# 1-Schematic_GPIO_WAVER.net
KiCad netlist of a schematic drawn in EasyEDA
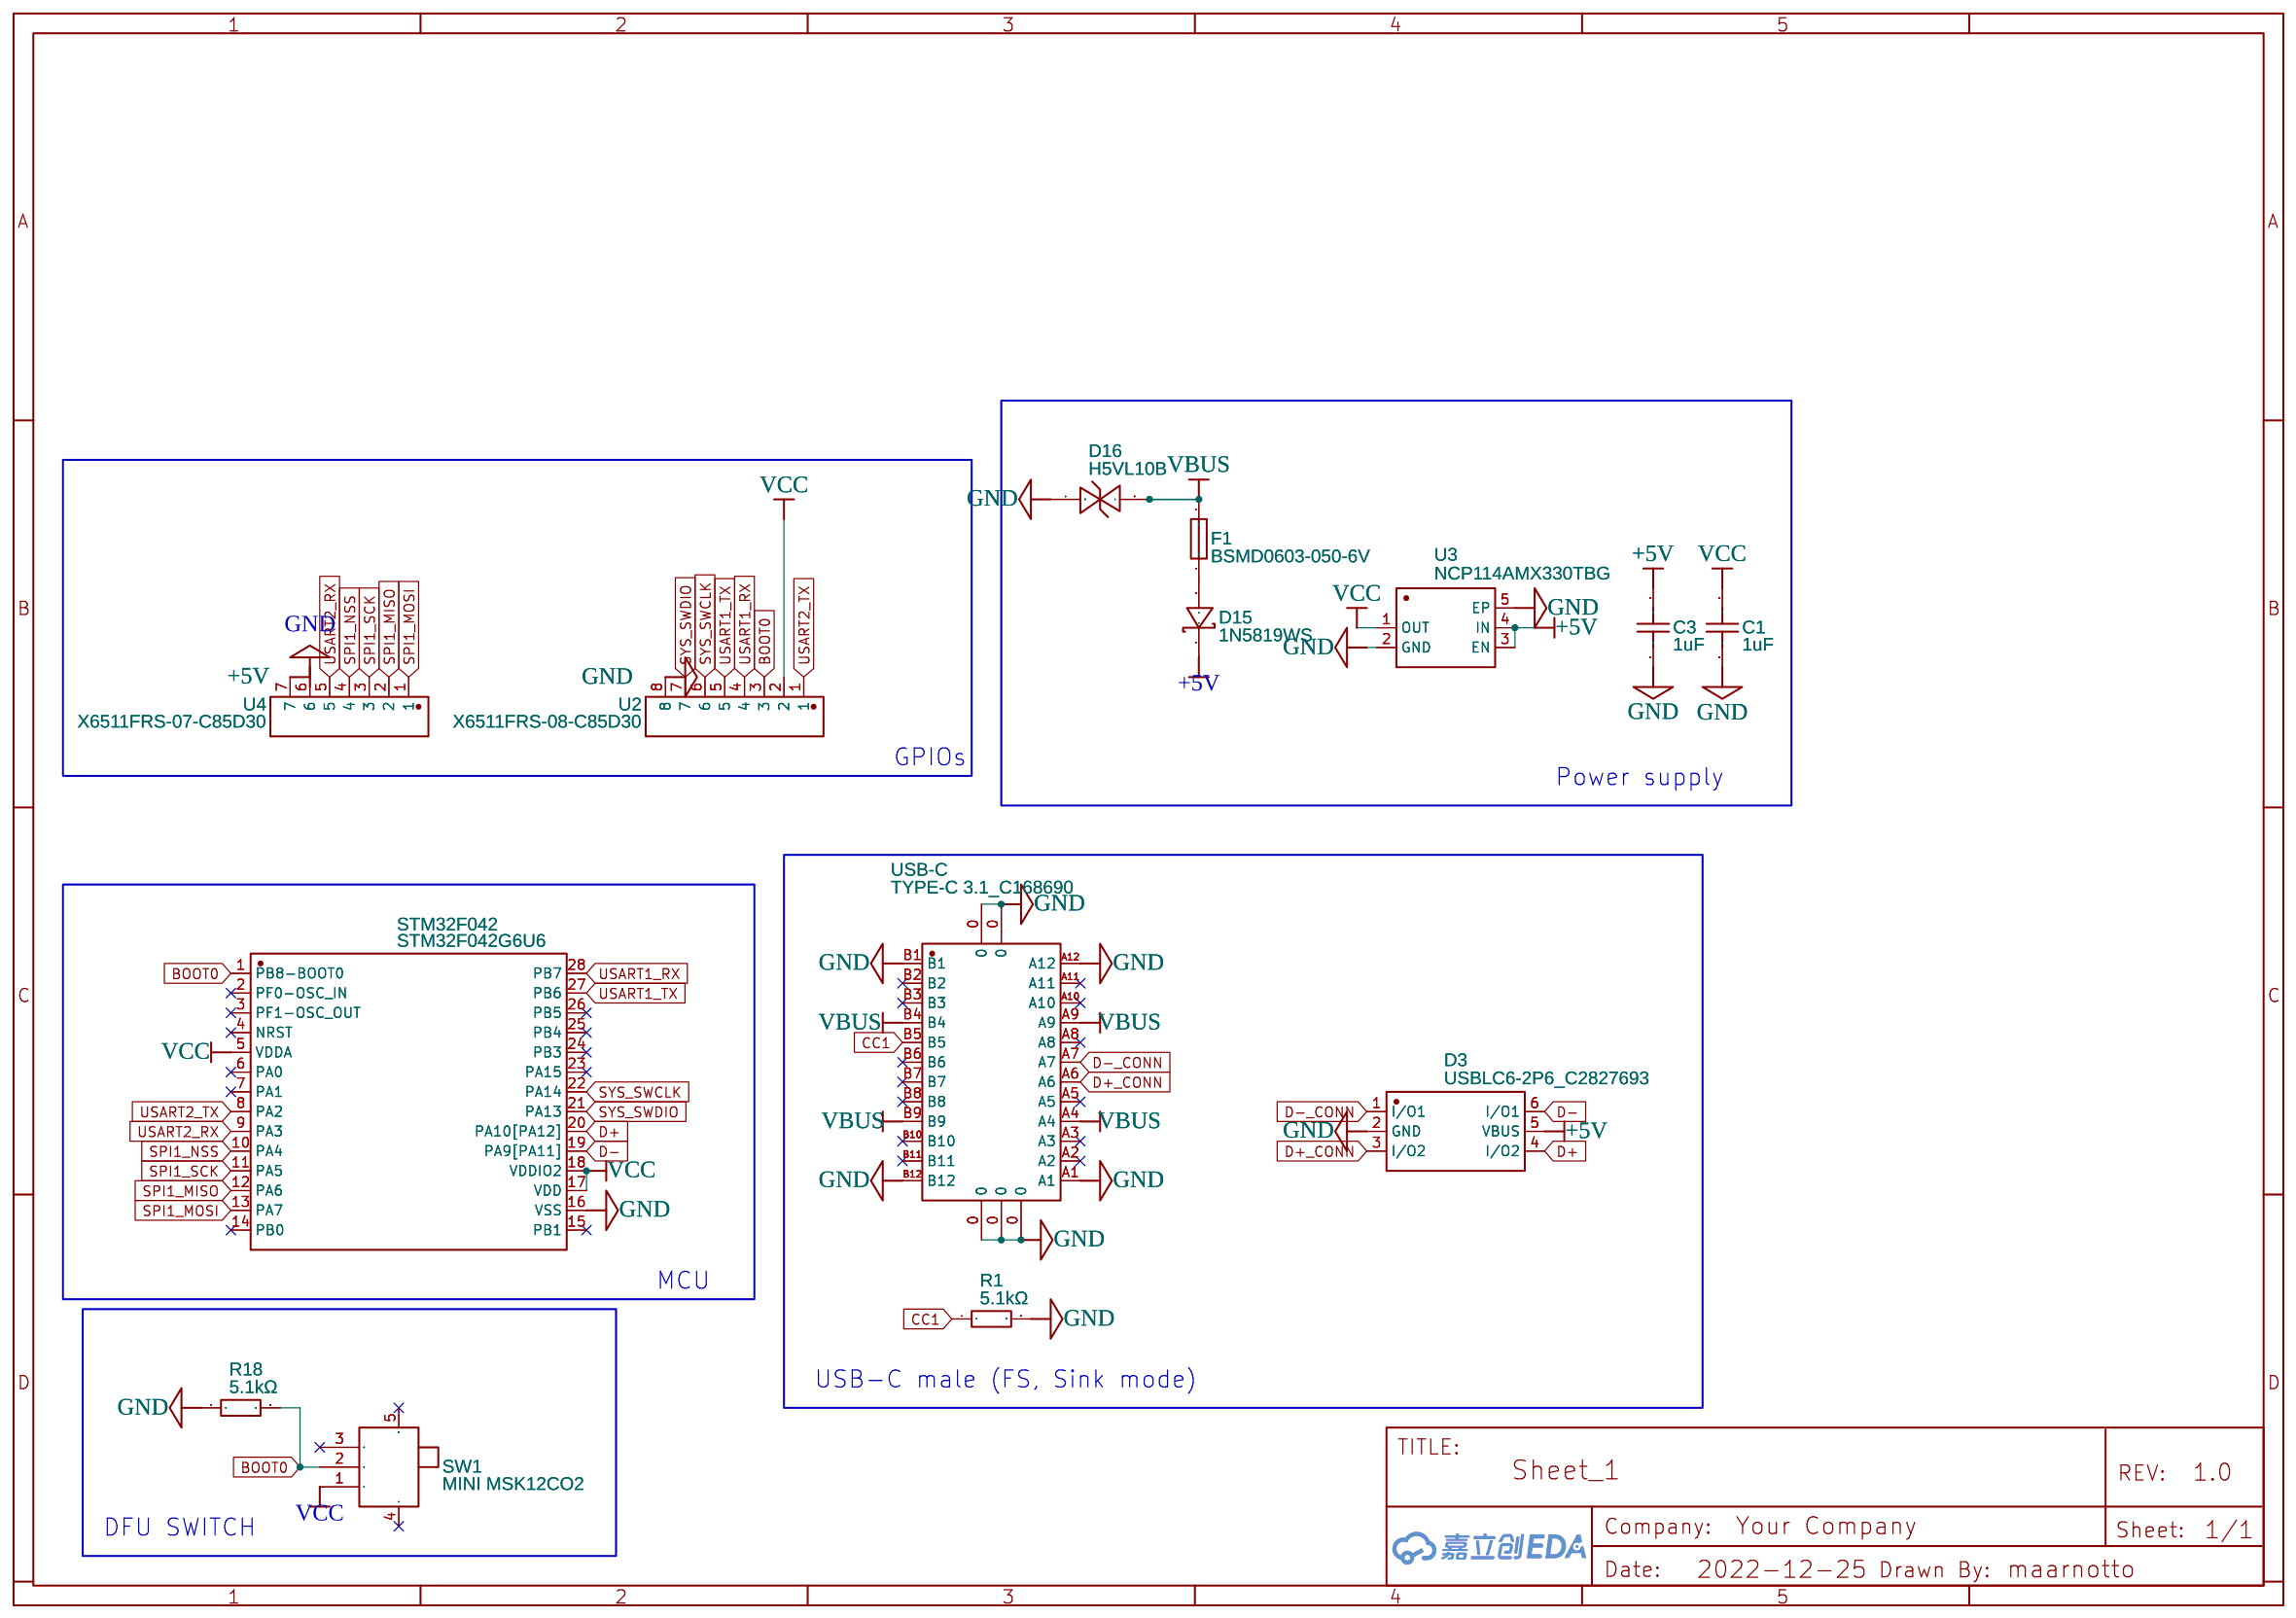
[diagram p0: schematic sheet]

(export (version "E")
  (design (tool "Eeschema 10.0.6"))
  (components
    (comp (ref "C1") (value "1uF") (libsource (lib "") (part "C_0603_US")))
    (comp (ref "C3") (value "1uF") (libsource (lib "") (part "C_0603_US")))
    (comp (ref "D3")
      (value "USBLC6-2P6_C2827693")
      (fields (field (name "Manufacturer Part") "USBLC6-2P6") (field (name "Manufacturer") "TECH PUBLIC(台舟)"))
      (libsource (lib "") (part "USBLC6-2P6_C2827693"))
    )
    (comp (ref "D15")
      (value "1N5819WS")
      (fields (field (name "Manufacturer") "Hottech(合科泰)"))
      (libsource (lib "") (part "1N5819WS"))
    )
    (comp (ref "D16")
      (value "H5VL10B")
      (fields (field (name "Manufacturer") "宏迦橙"))
      (libsource (lib "") (part "H5VL10B"))
    )
    (comp (ref "F1")
      (value "BSMD0603-050-6V")
      (fields (field (name "Manufacturer") "BHFUSE(佰宏)"))
      (libsource (lib "") (part "BSMD0603-050-6V"))
    )
    (comp (ref "R1")
      (value "5.1kΩ")
      (fields
        (field (name "Manufacturer Part") "0402WGF5101TCE")
        (field (name "Manufacturer") "UNI-ROYAL(厚声)")
      )
      (libsource (lib "") (part "0402WGF5101TCE"))
    )
    (comp (ref "R18")
      (value "5.1kΩ")
      (fields
        (field (name "Manufacturer Part") "0402WGF5101TCE")
        (field (name "Manufacturer") "UNI-ROYAL(厚声)")
      )
      (libsource (lib "") (part "0402WGF5101TCE"))
    )
    (comp (ref "STM32F042")
      (value "STM32F042G6U6")
      (fields (field (name "Manufacturer") "ST(意法半导体)"))
      (libsource (lib "") (part "STM32F042G6U6"))
    )
    (comp (ref "SW1")
      (value "MINI MSK12CO2")
      (fields (field (name "Manufacturer") "SHOU HAN(首韩)"))
      (libsource (lib "") (part "MINI MSK12CO2"))
    )
    (comp (ref "U2")
      (value "X6511FRS-08-C85D30")
      (fields (field (name "Manufacturer") "XKB Connectivity(中国星坤)"))
      (libsource (lib "") (part "X6511FRS-08-C85D30"))
    )
    (comp (ref "U3")
      (value "NCP114AMX330TBG")
      (fields (field (name "Manufacturer") "onsemi(安森美)"))
      (libsource (lib "") (part "NCP114AMX330TBG"))
    )
    (comp (ref "U4")
      (value "X6511FRS-07-C85D30")
      (fields (field (name "Manufacturer") "XKB Connectivity(中国星坤)"))
      (libsource (lib "") (part "X6511FRS-07-C85D30"))
    )
    (comp (ref "USB-C")
      (value "TYPE-C 3.1_C168690")
      (fields (field (name "Manufacturer Part") "918-118A2021Y40000") (field (name "Manufacturer") "精拓金"))
      (libsource (lib "") (part "TYPE-C 3.1_C168690"))
    )
  )
  (nets
    (net (code "1") (name "+5V") (class "Default")
      (node (ref "C3") (pin "2") (pinfunction "2_2") (pintype "unspecified"))
      (node (ref "D15") (pin "1") (pinfunction "K_1") (pintype "unspecified"))
      (node (ref "D3") (pin "5") (pinfunction "VBUS_5") (pintype "unspecified"))
      (node (ref "U3") (pin "3") (pinfunction "EN_3") (pintype "unspecified"))
      (node (ref "U3") (pin "4") (pinfunction "IN_4") (pintype "unspecified"))
      (node (ref "U4") (pin "7") (pinfunction "7_7") (pintype "unspecified"))
    )
    (net (code "2") (name "BOOT0") (class "Default")
      (node (ref "R18") (pin "2") (pinfunction "2_2") (pintype "input"))
      (node (ref "STM32F042") (pin "1") (pinfunction "PB8-BOOT0_1") (pintype "unspecified"))
      (node (ref "SW1") (pin "2") (pinfunction "2_2") (pintype "unspecified"))
      (node (ref "U2") (pin "3") (pinfunction "3_3") (pintype "unspecified"))
    )
    (net (code "3") (name "CC1") (class "Default")
      (node (ref "R1") (pin "1") (pinfunction "1_1") (pintype "input"))
      (node (ref "USB-C") (pin "B5") (pinfunction "B5_B5") (pintype "unspecified"))
    )
    (net (code "4") (name "D+") (class "Default")
      (node (ref "D3") (pin "4") (pinfunction "I/O2_4") (pintype "unspecified"))
      (node (ref "STM32F042") (pin "20") (pinfunction "PA10[PA12]_20") (pintype "unspecified"))
    )
    (net (code "5") (name "D+_CONN") (class "Default")
      (node (ref "D3") (pin "3") (pinfunction "I/O2_3") (pintype "unspecified"))
      (node (ref "USB-C") (pin "A6") (pinfunction "A6_A6") (pintype "unspecified"))
    )
    (net (code "6") (name "D-") (class "Default")
      (node (ref "D3") (pin "6") (pinfunction "I/O1_6") (pintype "unspecified"))
      (node (ref "STM32F042") (pin "19") (pinfunction "PA9[PA11]_19") (pintype "unspecified"))
    )
    (net (code "7") (name "D-_CONN") (class "Default")
      (node (ref "D3") (pin "1") (pinfunction "I/O1_1") (pintype "unspecified"))
      (node (ref "USB-C") (pin "A7") (pinfunction "A7_A7") (pintype "unspecified"))
    )
    (net (code "8") (name "GND") (class "Default")
      (node (ref "C1") (pin "1") (pinfunction "1_1") (pintype "unspecified"))
      (node (ref "C3") (pin "1") (pinfunction "1_1") (pintype "unspecified"))
      (node (ref "D16") (pin "1") (pinfunction "C_1") (pintype "unspecified"))
      (node (ref "D3") (pin "2") (pinfunction "GND_2") (pintype "unspecified"))
      (node (ref "R1") (pin "2") (pinfunction "2_2") (pintype "input"))
      (node (ref "R18") (pin "1") (pinfunction "1_1") (pintype "input"))
      (node (ref "STM32F042") (pin "16") (pinfunction "VSS_16") (pintype "unspecified"))
      (node (ref "U2") (pin "8") (pinfunction "8_8") (pintype "unspecified"))
      (node (ref "U3") (pin "2") (pinfunction "GND_2") (pintype "unspecified"))
      (node (ref "U3") (pin "5") (pinfunction "EP_5") (pintype "unspecified"))
      (node (ref "U4") (pin "6") (pinfunction "6_6") (pintype "unspecified"))
      (node (ref "USB-C") (pin "0") (pinfunction "0_0") (pintype "unspecified"))
      (node (ref "USB-C") (pin "A1") (pinfunction "A1_A1") (pintype "unspecified"))
      (node (ref "USB-C") (pin "A12") (pinfunction "A12_A12") (pintype "unspecified"))
      (node (ref "USB-C") (pin "B1") (pinfunction "B1_B1") (pintype "unspecified"))
      (node (ref "USB-C") (pin "B12") (pinfunction "B12_B12") (pintype "unspecified"))
    )
    (net (code "9") (name "Net-(D15-A)") (class "Default")
      (node (ref "D15") (pin "2") (pinfunction "A_2") (pintype "unspecified"))
      (node (ref "F1") (pin "1") (pinfunction "1_1") (pintype "unspecified"))
    )
    (net (code "10") (name "SPI1_MISO") (class "Default")
      (node (ref "STM32F042") (pin "12") (pinfunction "PA6_12") (pintype "unspecified"))
      (node (ref "U4") (pin "2") (pinfunction "2_2") (pintype "unspecified"))
    )
    (net (code "11") (name "SPI1_MOSI") (class "Default")
      (node (ref "STM32F042") (pin "13") (pinfunction "PA7_13") (pintype "unspecified"))
      (node (ref "U4") (pin "1") (pinfunction "1_1") (pintype "unspecified"))
    )
    (net (code "12") (name "SPI1_NSS") (class "Default")
      (node (ref "STM32F042") (pin "10") (pinfunction "PA4_10") (pintype "unspecified"))
      (node (ref "U4") (pin "4") (pinfunction "4_4") (pintype "unspecified"))
    )
    (net (code "13") (name "SPI1_SCK") (class "Default")
      (node (ref "STM32F042") (pin "11") (pinfunction "PA5_11") (pintype "unspecified"))
      (node (ref "U4") (pin "3") (pinfunction "3_3") (pintype "unspecified"))
    )
    (net (code "14") (name "SYS_SWCLK") (class "Default")
      (node (ref "STM32F042") (pin "22") (pinfunction "PA14_22") (pintype "unspecified"))
      (node (ref "U2") (pin "6") (pinfunction "6_6") (pintype "unspecified"))
    )
    (net (code "15") (name "SYS_SWDIO") (class "Default")
      (node (ref "STM32F042") (pin "21") (pinfunction "PA13_21") (pintype "unspecified"))
      (node (ref "U2") (pin "7") (pinfunction "7_7") (pintype "unspecified"))
    )
    (net (code "16") (name "USART1_RX") (class "Default")
      (node (ref "STM32F042") (pin "28") (pinfunction "PB7_28") (pintype "unspecified"))
      (node (ref "U2") (pin "4") (pinfunction "4_4") (pintype "unspecified"))
    )
    (net (code "17") (name "USART1_TX") (class "Default")
      (node (ref "STM32F042") (pin "27") (pinfunction "PB6_27") (pintype "unspecified"))
      (node (ref "U2") (pin "5") (pinfunction "5_5") (pintype "unspecified"))
    )
    (net (code "18") (name "USART2_RX") (class "Default")
      (node (ref "STM32F042") (pin "9") (pinfunction "PA3_9") (pintype "unspecified"))
      (node (ref "U4") (pin "5") (pinfunction "5_5") (pintype "unspecified"))
    )
    (net (code "19") (name "USART2_TX") (class "Default")
      (node (ref "STM32F042") (pin "8") (pinfunction "PA2_8") (pintype "unspecified"))
      (node (ref "U2") (pin "1") (pinfunction "1_1") (pintype "unspecified"))
    )
    (net (code "20") (name "VBUS") (class "Default")
      (node (ref "D16") (pin "2") (pinfunction "A_2") (pintype "unspecified"))
      (node (ref "F1") (pin "2") (pinfunction "2_2") (pintype "unspecified"))
      (node (ref "USB-C") (pin "A4") (pinfunction "A4_A4") (pintype "unspecified"))
      (node (ref "USB-C") (pin "A9") (pinfunction "A9_A9") (pintype "unspecified"))
      (node (ref "USB-C") (pin "B4") (pinfunction "B4_B4") (pintype "unspecified"))
      (node (ref "USB-C") (pin "B9") (pinfunction "B9_B9") (pintype "unspecified"))
    )
    (net (code "21") (name "VCC") (class "Default")
      (node (ref "C1") (pin "2") (pinfunction "2_2") (pintype "unspecified"))
      (node (ref "STM32F042") (pin "17") (pinfunction "VDD_17") (pintype "unspecified"))
      (node (ref "STM32F042") (pin "18") (pinfunction "VDDIO2_18") (pintype "unspecified"))
      (node (ref "STM32F042") (pin "5") (pinfunction "VDDA_5") (pintype "unspecified"))
      (node (ref "SW1") (pin "1") (pinfunction "1_1") (pintype "unspecified"))
      (node (ref "U2") (pin "2") (pinfunction "2_2") (pintype "unspecified"))
      (node (ref "U3") (pin "1") (pinfunction "OUT_1") (pintype "unspecified"))
    )
    (net (code "22") (name "unconnected-(STM32F042-NRST-Pad4)") (class "Default")
      (node (ref "STM32F042") (pin "4") (pinfunction "NRST_4") (pintype "unspecified+no_connect"))
    )
    (net (code "23") (name "unconnected-(STM32F042-PA0-Pad6)") (class "Default")
      (node (ref "STM32F042") (pin "6") (pinfunction "PA0_6") (pintype "unspecified+no_connect"))
    )
    (net (code "24") (name "unconnected-(STM32F042-PA1-Pad7)") (class "Default")
      (node (ref "STM32F042") (pin "7") (pinfunction "PA1_7") (pintype "unspecified+no_connect"))
    )
    (net (code "25") (name "unconnected-(STM32F042-PA15-Pad23)") (class "Default")
      (node (ref "STM32F042") (pin "23") (pinfunction "PA15_23") (pintype "unspecified+no_connect"))
    )
    (net (code "26") (name "unconnected-(STM32F042-PB0-Pad14)") (class "Default")
      (node (ref "STM32F042") (pin "14") (pinfunction "PB0_14") (pintype "unspecified+no_connect"))
    )
    (net (code "27") (name "unconnected-(STM32F042-PB1-Pad15)") (class "Default")
      (node (ref "STM32F042") (pin "15") (pinfunction "PB1_15") (pintype "unspecified+no_connect"))
    )
    (net (code "28") (name "unconnected-(STM32F042-PB3-Pad24)") (class "Default")
      (node (ref "STM32F042") (pin "24") (pinfunction "PB3_24") (pintype "unspecified+no_connect"))
    )
    (net (code "29") (name "unconnected-(STM32F042-PB4-Pad25)") (class "Default")
      (node (ref "STM32F042") (pin "25") (pinfunction "PB4_25") (pintype "unspecified+no_connect"))
    )
    (net (code "30") (name "unconnected-(STM32F042-PB5-Pad26)") (class "Default")
      (node (ref "STM32F042") (pin "26") (pinfunction "PB5_26") (pintype "unspecified+no_connect"))
    )
    (net (code "31") (name "unconnected-(STM32F042-PF0-OSC_IN-Pad2)") (class "Default")
      (node (ref "STM32F042") (pin "2") (pinfunction "PF0-OSC_IN_2") (pintype "unspecified+no_connect"))
    )
    (net (code "32") (name "unconnected-(STM32F042-PF1-OSC_OUT-Pad3)") (class "Default")
      (node (ref "STM32F042") (pin "3") (pinfunction "PF1-OSC_OUT_3") (pintype "unspecified+no_connect"))
    )
    (net (code "33") (name "unconnected-(SW1-Pad3)") (class "Default")
      (node (ref "SW1") (pin "3") (pinfunction "3_3") (pintype "unspecified+no_connect"))
    )
    (net (code "34") (name "unconnected-(SW1-Pad4)") (class "Default")
      (node (ref "SW1") (pin "4") (pinfunction "4_4") (pintype "unspecified+no_connect"))
    )
    (net (code "35") (name "unconnected-(SW1-Pad5)") (class "Default")
      (node (ref "SW1") (pin "5") (pinfunction "5_5") (pintype "unspecified+no_connect"))
    )
    (net (code "36") (name "unconnected-(USB-C-PadA2)") (class "Default")
      (node (ref "USB-C") (pin "A2") (pinfunction "A2_A2") (pintype "unspecified+no_connect"))
    )
    (net (code "37") (name "unconnected-(USB-C-PadA3)") (class "Default")
      (node (ref "USB-C") (pin "A3") (pinfunction "A3_A3") (pintype "unspecified+no_connect"))
    )
    (net (code "38") (name "unconnected-(USB-C-PadA5)") (class "Default")
      (node (ref "USB-C") (pin "A5") (pinfunction "A5_A5") (pintype "unspecified+no_connect"))
    )
    (net (code "39") (name "unconnected-(USB-C-PadA8)") (class "Default")
      (node (ref "USB-C") (pin "A8") (pinfunction "A8_A8") (pintype "unspecified+no_connect"))
    )
    (net (code "40") (name "unconnected-(USB-C-PadA10)") (class "Default")
      (node (ref "USB-C") (pin "A10") (pinfunction "A10_A10") (pintype "unspecified+no_connect"))
    )
    (net (code "41") (name "unconnected-(USB-C-PadA11)") (class "Default")
      (node (ref "USB-C") (pin "A11") (pinfunction "A11_A11") (pintype "unspecified+no_connect"))
    )
    (net (code "42") (name "unconnected-(USB-C-PadB2)") (class "Default")
      (node (ref "USB-C") (pin "B2") (pinfunction "B2_B2") (pintype "unspecified+no_connect"))
    )
    (net (code "43") (name "unconnected-(USB-C-PadB3)") (class "Default")
      (node (ref "USB-C") (pin "B3") (pinfunction "B3_B3") (pintype "unspecified+no_connect"))
    )
    (net (code "44") (name "unconnected-(USB-C-PadB6)") (class "Default")
      (node (ref "USB-C") (pin "B6") (pinfunction "B6_B6") (pintype "unspecified+no_connect"))
    )
    (net (code "45") (name "unconnected-(USB-C-PadB7)") (class "Default")
      (node (ref "USB-C") (pin "B7") (pinfunction "B7_B7") (pintype "unspecified+no_connect"))
    )
    (net (code "46") (name "unconnected-(USB-C-PadB8)") (class "Default")
      (node (ref "USB-C") (pin "B8") (pinfunction "B8_B8") (pintype "unspecified+no_connect"))
    )
    (net (code "47") (name "unconnected-(USB-C-PadB10)") (class "Default")
      (node (ref "USB-C") (pin "B10") (pinfunction "B10_B10") (pintype "unspecified+no_connect"))
    )
    (net (code "48") (name "unconnected-(USB-C-PadB11)") (class "Default")
      (node (ref "USB-C") (pin "B11") (pinfunction "B11_B11") (pintype "unspecified+no_connect"))
    )
  )
)
